# BBB_cape.net
KiCad netlist of a schematic drawn in EAGLE
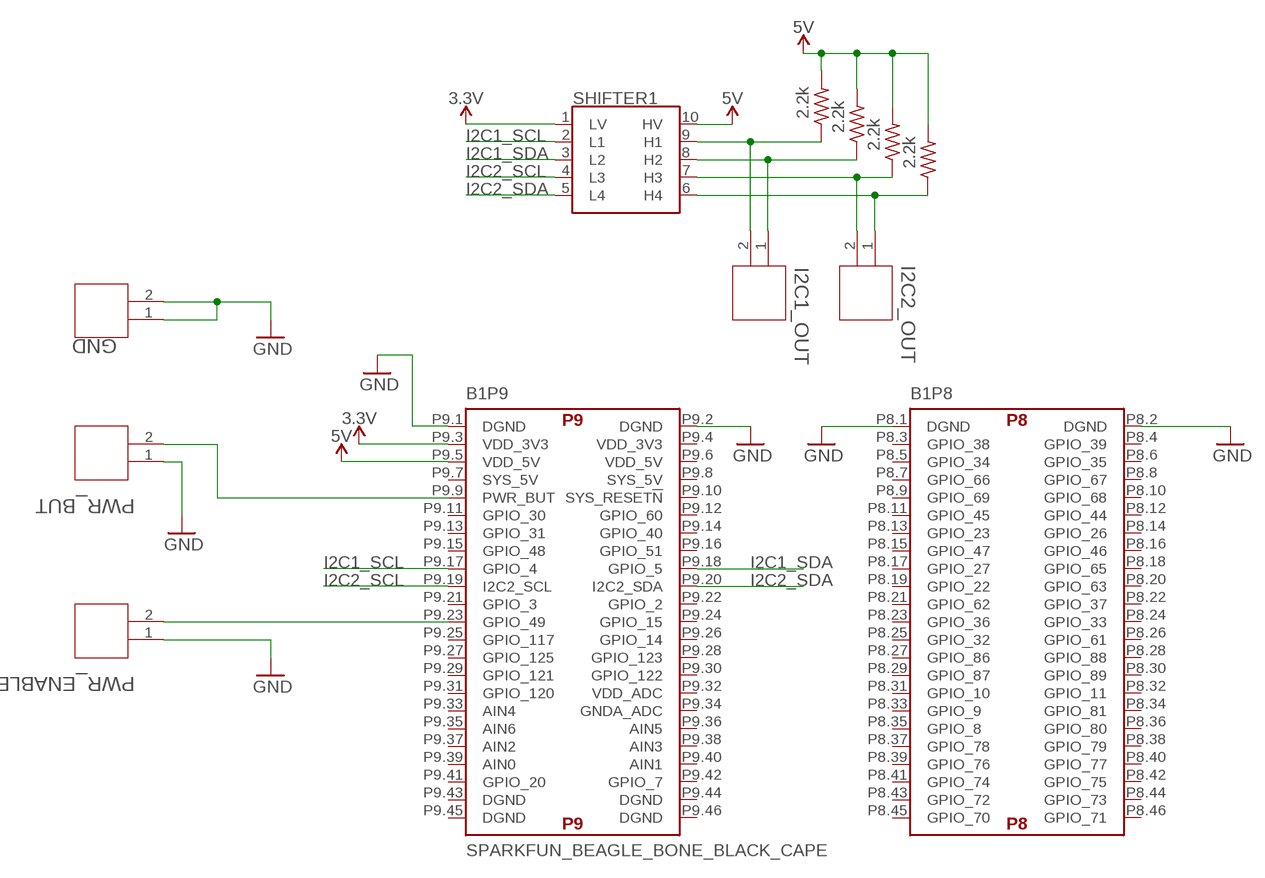
[diagram p0: schematic, sheet 1]

(export (version "E")
  (design (tool "Eeschema 10.0.6"))
  (components
    (comp (ref "B1")
      (value "SPARKFUN_BEAGLE_BONE_BLACK_CAPE")
      (footprint "eagle-import:BEAGLE_BONE_BLACK_CAPE")
      (libsource (lib "eagle-import") (part "SPARKFUN_BEAGLE_BONE_BLACK_CAPE"))
    )
    (comp (ref "GND")
      (value "PHOENIX_CONTACT_1758018")
      (footprint "eagle-import:PHOENIX_CONTACT_1758018")
      (fields
        (field (name "MANUFACTURER_PART_NUMBER") "1758018")
        (field (name "COPYRIGHT") "Copyright (C) 2018 Accelerated Designs. All rights reserved")
      )
      (libsource (lib "eagle-import") (part "PHOENIX_CONTACT_1758018"))
    )
    (comp (ref "I2C1_OUT")
      (value "PHOENIX_CONTACT_1758018")
      (footprint "eagle-import:PHOENIX_CONTACT_1758018")
      (fields
        (field (name "MANUFACTURER_PART_NUMBER") "1758018")
        (field (name "COPYRIGHT") "Copyright (C) 2018 Accelerated Designs. All rights reserved")
      )
      (libsource (lib "eagle-import") (part "PHOENIX_CONTACT_1758018"))
    )
    (comp (ref "I2C2_OUT")
      (value "PHOENIX_CONTACT_1758018")
      (footprint "eagle-import:PHOENIX_CONTACT_1758018")
      (fields
        (field (name "MANUFACTURER_PART_NUMBER") "1758018")
        (field (name "COPYRIGHT") "Copyright (C) 2018 Accelerated Designs. All rights reserved")
      )
      (libsource (lib "eagle-import") (part "PHOENIX_CONTACT_1758018"))
    )
    (comp (ref "PWR_BUT")
      (value "PHOENIX_CONTACT_1758018")
      (footprint "eagle-import:PHOENIX_CONTACT_1758018")
      (fields
        (field (name "MANUFACTURER_PART_NUMBER") "1758018")
        (field (name "COPYRIGHT") "Copyright (C) 2018 Accelerated Designs. All rights reserved")
      )
      (libsource (lib "eagle-import") (part "PHOENIX_CONTACT_1758018"))
    )
    (comp (ref "PWR_ENABLE")
      (value "PHOENIX_CONTACT_1758018")
      (footprint "eagle-import:PHOENIX_CONTACT_1758018")
      (fields
        (field (name "MANUFACTURER_PART_NUMBER") "1758018")
        (field (name "COPYRIGHT") "Copyright (C) 2018 Accelerated Designs. All rights reserved")
      )
      (libsource (lib "eagle-import") (part "PHOENIX_CONTACT_1758018"))
    )
    (comp (ref "R1")
      (value "2.2k")
      (footprint "eagle-import:0204_7")
      (libsource (lib "eagle-import") (part "R-US_0204/7"))
    )
    (comp (ref "R2")
      (value "2.2k")
      (footprint "eagle-import:0204_7")
      (libsource (lib "eagle-import") (part "R-US_0204/7"))
    )
    (comp (ref "R3")
      (value "2.2k")
      (footprint "eagle-import:0204_7")
      (libsource (lib "eagle-import") (part "R-US_0204/7"))
    )
    (comp (ref "R4")
      (value "2.2k")
      (footprint "eagle-import:0204_7")
      (libsource (lib "eagle-import") (part "R-US_0204/7"))
    )
    (comp (ref "SHIFTER1")
      (value "POLOLU_LOGIC_SHIFTERPOLOLU")
      (footprint "eagle-import:POLOLU_LOGIC_SHIFTER")
      (libsource (lib "eagle-import") (part "POLOLU_LOGIC_SHIFTERPOLOLU"))
    )
  )
  (nets
    (net (code "1") (name "/I2C1_SCL") (class "Default")
      (node (ref "B1") (pin "P9.17") (pinfunction "GPIO_4_P9.17") (pintype "bidirectional"))
      (node (ref "SHIFTER1") (pin "2") (pinfunction "L1_2") (pintype "bidirectional"))
    )
    (net (code "2") (name "/I2C1_SDA") (class "Default")
      (node (ref "B1") (pin "P9.18") (pinfunction "GPIO_5_P9.18") (pintype "bidirectional"))
      (node (ref "SHIFTER1") (pin "3") (pinfunction "L2_3") (pintype "bidirectional"))
    )
    (net (code "3") (name "/I2C2_SCL") (class "Default")
      (node (ref "B1") (pin "P9.19") (pinfunction "I2C2_SCL_P9.19") (pintype "bidirectional"))
      (node (ref "SHIFTER1") (pin "4") (pinfunction "L3_4") (pintype "bidirectional"))
    )
    (net (code "4") (name "/I2C2_SDA") (class "Default")
      (node (ref "B1") (pin "P9.20") (pinfunction "I2C2_SDA_P9.20") (pintype "bidirectional"))
      (node (ref "SHIFTER1") (pin "5") (pinfunction "L4_5") (pintype "bidirectional"))
    )
    (net (code "5") (name "3.3V") (class "Default")
      (node (ref "B1") (pin "P9.3") (pinfunction "VDD_3V3_P9.3") (pintype "bidirectional"))
      (node (ref "SHIFTER1") (pin "1") (pinfunction "LV_1") (pintype "input"))
    )
    (net (code "6") (name "5V") (class "Default")
      (node (ref "B1") (pin "P9.5") (pinfunction "VDD_5V_P9.5") (pintype "bidirectional"))
      (node (ref "R1") (pin "2") (pinfunction "2_2") (pintype "passive"))
      (node (ref "R2") (pin "2") (pinfunction "2_2") (pintype "passive"))
      (node (ref "R3") (pin "2") (pinfunction "2_2") (pintype "passive"))
      (node (ref "R4") (pin "2") (pinfunction "2_2") (pintype "passive"))
      (node (ref "SHIFTER1") (pin "10") (pinfunction "HV_10") (pintype "input"))
    )
    (net (code "7") (name "GND") (class "Default")
      (node (ref "B1") (pin "P8.1") (pinfunction "DGND_P8.1") (pintype "bidirectional"))
      (node (ref "B1") (pin "P8.2") (pinfunction "DGND_P8.2") (pintype "bidirectional"))
      (node (ref "B1") (pin "P9.1") (pinfunction "DGND_P9.1") (pintype "bidirectional"))
      (node (ref "B1") (pin "P9.2") (pinfunction "DGND_P9.2") (pintype "bidirectional"))
      (node (ref "GND") (pin "1") (pinfunction "1_1") (pintype "passive"))
      (node (ref "GND") (pin "2") (pinfunction "2_2") (pintype "passive"))
      (node (ref "PWR_BUT") (pin "1") (pinfunction "1_1") (pintype "passive"))
      (node (ref "PWR_ENABLE") (pin "1") (pinfunction "1_1") (pintype "passive"))
    )
    (net (code "8") (name "Net-(B1B-GPIO_49)") (class "Default")
      (node (ref "B1") (pin "P9.23") (pinfunction "GPIO_49_P9.23") (pintype "bidirectional"))
      (node (ref "PWR_ENABLE") (pin "2") (pinfunction "2_2") (pintype "passive"))
    )
    (net (code "9") (name "Net-(B1B-PWR_BUT)") (class "Default")
      (node (ref "B1") (pin "P9.9") (pinfunction "PWR_BUT_P9.9") (pintype "bidirectional"))
      (node (ref "PWR_BUT") (pin "2") (pinfunction "2_2") (pintype "passive"))
    )
    (net (code "10") (name "Net-(SHIFTER1-H1)") (class "Default")
      (node (ref "I2C1_OUT") (pin "2") (pinfunction "2_2") (pintype "passive"))
      (node (ref "R1") (pin "1") (pinfunction "1_1") (pintype "passive"))
      (node (ref "SHIFTER1") (pin "9") (pinfunction "H1_9") (pintype "bidirectional"))
    )
    (net (code "11") (name "Net-(SHIFTER1-H2)") (class "Default")
      (node (ref "I2C1_OUT") (pin "1") (pinfunction "1_1") (pintype "passive"))
      (node (ref "R2") (pin "1") (pinfunction "1_1") (pintype "passive"))
      (node (ref "SHIFTER1") (pin "8") (pinfunction "H2_8") (pintype "bidirectional"))
    )
    (net (code "12") (name "Net-(SHIFTER1-H3)") (class "Default")
      (node (ref "I2C2_OUT") (pin "2") (pinfunction "2_2") (pintype "passive"))
      (node (ref "R3") (pin "1") (pinfunction "1_1") (pintype "passive"))
      (node (ref "SHIFTER1") (pin "7") (pinfunction "H3_7") (pintype "bidirectional"))
    )
    (net (code "13") (name "Net-(SHIFTER1-H4)") (class "Default")
      (node (ref "I2C2_OUT") (pin "1") (pinfunction "1_1") (pintype "passive"))
      (node (ref "R4") (pin "1") (pinfunction "1_1") (pintype "passive"))
      (node (ref "SHIFTER1") (pin "6") (pinfunction "H4_6") (pintype "bidirectional"))
    )
    (net (code "14") (name "unconnected-(B1A-GPIO_8-PadP8.35)") (class "Default")
      (node (ref "B1") (pin "P8.35") (pinfunction "GPIO_8_P8.35") (pintype "bidirectional"))
    )
    (net (code "15") (name "unconnected-(B1A-GPIO_9-PadP8.33)") (class "Default")
      (node (ref "B1") (pin "P8.33") (pinfunction "GPIO_9_P8.33") (pintype "bidirectional"))
    )
    (net (code "16") (name "unconnected-(B1A-GPIO_10-PadP8.31)") (class "Default")
      (node (ref "B1") (pin "P8.31") (pinfunction "GPIO_10_P8.31") (pintype "bidirectional"))
    )
    (net (code "17") (name "unconnected-(B1A-GPIO_11-PadP8.32)") (class "Default")
      (node (ref "B1") (pin "P8.32") (pinfunction "GPIO_11_P8.32") (pintype "bidirectional"))
    )
    (net (code "18") (name "unconnected-(B1A-GPIO_22-PadP8.19)") (class "Default")
      (node (ref "B1") (pin "P8.19") (pinfunction "GPIO_22_P8.19") (pintype "bidirectional"))
    )
    (net (code "19") (name "unconnected-(B1A-GPIO_23-PadP8.13)") (class "Default")
      (node (ref "B1") (pin "P8.13") (pinfunction "GPIO_23_P8.13") (pintype "bidirectional"))
    )
    (net (code "20") (name "unconnected-(B1A-GPIO_26-PadP8.14)") (class "Default")
      (node (ref "B1") (pin "P8.14") (pinfunction "GPIO_26_P8.14") (pintype "bidirectional"))
    )
    (net (code "21") (name "unconnected-(B1A-GPIO_27-PadP8.17)") (class "Default")
      (node (ref "B1") (pin "P8.17") (pinfunction "GPIO_27_P8.17") (pintype "bidirectional"))
    )
    (net (code "22") (name "unconnected-(B1A-GPIO_32-PadP8.25)") (class "Default")
      (node (ref "B1") (pin "P8.25") (pinfunction "GPIO_32_P8.25") (pintype "bidirectional"))
    )
    (net (code "23") (name "unconnected-(B1A-GPIO_33-PadP8.24)") (class "Default")
      (node (ref "B1") (pin "P8.24") (pinfunction "GPIO_33_P8.24") (pintype "bidirectional"))
    )
    (net (code "24") (name "unconnected-(B1A-GPIO_34-PadP8.5)") (class "Default")
      (node (ref "B1") (pin "P8.5") (pinfunction "GPIO_34_P8.5") (pintype "bidirectional"))
    )
    (net (code "25") (name "unconnected-(B1A-GPIO_35-PadP8.6)") (class "Default")
      (node (ref "B1") (pin "P8.6") (pinfunction "GPIO_35_P8.6") (pintype "bidirectional"))
    )
    (net (code "26") (name "unconnected-(B1A-GPIO_36-PadP8.23)") (class "Default")
      (node (ref "B1") (pin "P8.23") (pinfunction "GPIO_36_P8.23") (pintype "bidirectional"))
    )
    (net (code "27") (name "unconnected-(B1A-GPIO_37-PadP8.22)") (class "Default")
      (node (ref "B1") (pin "P8.22") (pinfunction "GPIO_37_P8.22") (pintype "bidirectional"))
    )
    (net (code "28") (name "unconnected-(B1A-GPIO_38-PadP8.3)") (class "Default")
      (node (ref "B1") (pin "P8.3") (pinfunction "GPIO_38_P8.3") (pintype "bidirectional"))
    )
    (net (code "29") (name "unconnected-(B1A-GPIO_39-PadP8.4)") (class "Default")
      (node (ref "B1") (pin "P8.4") (pinfunction "GPIO_39_P8.4") (pintype "bidirectional"))
    )
    (net (code "30") (name "unconnected-(B1A-GPIO_44-PadP8.12)") (class "Default")
      (node (ref "B1") (pin "P8.12") (pinfunction "GPIO_44_P8.12") (pintype "bidirectional"))
    )
    (net (code "31") (name "unconnected-(B1A-GPIO_45-PadP8.11)") (class "Default")
      (node (ref "B1") (pin "P8.11") (pinfunction "GPIO_45_P8.11") (pintype "bidirectional"))
    )
    (net (code "32") (name "unconnected-(B1A-GPIO_46-PadP8.16)") (class "Default")
      (node (ref "B1") (pin "P8.16") (pinfunction "GPIO_46_P8.16") (pintype "bidirectional"))
    )
    (net (code "33") (name "unconnected-(B1A-GPIO_47-PadP8.15)") (class "Default")
      (node (ref "B1") (pin "P8.15") (pinfunction "GPIO_47_P8.15") (pintype "bidirectional"))
    )
    (net (code "34") (name "unconnected-(B1A-GPIO_61-PadP8.26)") (class "Default")
      (node (ref "B1") (pin "P8.26") (pinfunction "GPIO_61_P8.26") (pintype "bidirectional"))
    )
    (net (code "35") (name "unconnected-(B1A-GPIO_62-PadP8.21)") (class "Default")
      (node (ref "B1") (pin "P8.21") (pinfunction "GPIO_62_P8.21") (pintype "bidirectional"))
    )
    (net (code "36") (name "unconnected-(B1A-GPIO_63-PadP8.20)") (class "Default")
      (node (ref "B1") (pin "P8.20") (pinfunction "GPIO_63_P8.20") (pintype "bidirectional"))
    )
    (net (code "37") (name "unconnected-(B1A-GPIO_65-PadP8.18)") (class "Default")
      (node (ref "B1") (pin "P8.18") (pinfunction "GPIO_65_P8.18") (pintype "bidirectional"))
    )
    (net (code "38") (name "unconnected-(B1A-GPIO_66-PadP8.7)") (class "Default")
      (node (ref "B1") (pin "P8.7") (pinfunction "GPIO_66_P8.7") (pintype "bidirectional"))
    )
    (net (code "39") (name "unconnected-(B1A-GPIO_67-PadP8.8)") (class "Default")
      (node (ref "B1") (pin "P8.8") (pinfunction "GPIO_67_P8.8") (pintype "bidirectional"))
    )
    (net (code "40") (name "unconnected-(B1A-GPIO_68-PadP8.10)") (class "Default")
      (node (ref "B1") (pin "P8.10") (pinfunction "GPIO_68_P8.10") (pintype "bidirectional"))
    )
    (net (code "41") (name "unconnected-(B1A-GPIO_69-PadP8.9)") (class "Default")
      (node (ref "B1") (pin "P8.9") (pinfunction "GPIO_69_P8.9") (pintype "bidirectional"))
    )
    (net (code "42") (name "unconnected-(B1A-GPIO_70-PadP8.45)") (class "Default")
      (node (ref "B1") (pin "P8.45") (pinfunction "GPIO_70_P8.45") (pintype "bidirectional"))
    )
    (net (code "43") (name "unconnected-(B1A-GPIO_71-PadP8.46)") (class "Default")
      (node (ref "B1") (pin "P8.46") (pinfunction "GPIO_71_P8.46") (pintype "bidirectional"))
    )
    (net (code "44") (name "unconnected-(B1A-GPIO_72-PadP8.43)") (class "Default")
      (node (ref "B1") (pin "P8.43") (pinfunction "GPIO_72_P8.43") (pintype "bidirectional"))
    )
    (net (code "45") (name "unconnected-(B1A-GPIO_73-PadP8.44)") (class "Default")
      (node (ref "B1") (pin "P8.44") (pinfunction "GPIO_73_P8.44") (pintype "bidirectional"))
    )
    (net (code "46") (name "unconnected-(B1A-GPIO_74-PadP8.41)") (class "Default")
      (node (ref "B1") (pin "P8.41") (pinfunction "GPIO_74_P8.41") (pintype "bidirectional"))
    )
    (net (code "47") (name "unconnected-(B1A-GPIO_75-PadP8.42)") (class "Default")
      (node (ref "B1") (pin "P8.42") (pinfunction "GPIO_75_P8.42") (pintype "bidirectional"))
    )
    (net (code "48") (name "unconnected-(B1A-GPIO_76-PadP8.39)") (class "Default")
      (node (ref "B1") (pin "P8.39") (pinfunction "GPIO_76_P8.39") (pintype "bidirectional"))
    )
    (net (code "49") (name "unconnected-(B1A-GPIO_77-PadP8.40)") (class "Default")
      (node (ref "B1") (pin "P8.40") (pinfunction "GPIO_77_P8.40") (pintype "bidirectional"))
    )
    (net (code "50") (name "unconnected-(B1A-GPIO_78-PadP8.37)") (class "Default")
      (node (ref "B1") (pin "P8.37") (pinfunction "GPIO_78_P8.37") (pintype "bidirectional"))
    )
    (net (code "51") (name "unconnected-(B1A-GPIO_79-PadP8.38)") (class "Default")
      (node (ref "B1") (pin "P8.38") (pinfunction "GPIO_79_P8.38") (pintype "bidirectional"))
    )
    (net (code "52") (name "unconnected-(B1A-GPIO_80-PadP8.36)") (class "Default")
      (node (ref "B1") (pin "P8.36") (pinfunction "GPIO_80_P8.36") (pintype "bidirectional"))
    )
    (net (code "53") (name "unconnected-(B1A-GPIO_81-PadP8.34)") (class "Default")
      (node (ref "B1") (pin "P8.34") (pinfunction "GPIO_81_P8.34") (pintype "bidirectional"))
    )
    (net (code "54") (name "unconnected-(B1A-GPIO_86-PadP8.27)") (class "Default")
      (node (ref "B1") (pin "P8.27") (pinfunction "GPIO_86_P8.27") (pintype "bidirectional"))
    )
    (net (code "55") (name "unconnected-(B1A-GPIO_87-PadP8.29)") (class "Default")
      (node (ref "B1") (pin "P8.29") (pinfunction "GPIO_87_P8.29") (pintype "bidirectional"))
    )
    (net (code "56") (name "unconnected-(B1A-GPIO_88-PadP8.28)") (class "Default")
      (node (ref "B1") (pin "P8.28") (pinfunction "GPIO_88_P8.28") (pintype "bidirectional"))
    )
    (net (code "57") (name "unconnected-(B1A-GPIO_89-PadP8.30)") (class "Default")
      (node (ref "B1") (pin "P8.30") (pinfunction "GPIO_89_P8.30") (pintype "bidirectional"))
    )
    (net (code "58") (name "unconnected-(B1B-AIN0-PadP9.39)") (class "Default")
      (node (ref "B1") (pin "P9.39") (pinfunction "AIN0_P9.39") (pintype "bidirectional"))
    )
    (net (code "59") (name "unconnected-(B1B-AIN1-PadP9.40)") (class "Default")
      (node (ref "B1") (pin "P9.40") (pinfunction "AIN1_P9.40") (pintype "bidirectional"))
    )
    (net (code "60") (name "unconnected-(B1B-AIN2-PadP9.37)") (class "Default")
      (node (ref "B1") (pin "P9.37") (pinfunction "AIN2_P9.37") (pintype "bidirectional"))
    )
    (net (code "61") (name "unconnected-(B1B-AIN3-PadP9.38)") (class "Default")
      (node (ref "B1") (pin "P9.38") (pinfunction "AIN3_P9.38") (pintype "bidirectional"))
    )
    (net (code "62") (name "unconnected-(B1B-AIN4-PadP9.33)") (class "Default")
      (node (ref "B1") (pin "P9.33") (pinfunction "AIN4_P9.33") (pintype "bidirectional"))
    )
    (net (code "63") (name "unconnected-(B1B-AIN5-PadP9.36)") (class "Default")
      (node (ref "B1") (pin "P9.36") (pinfunction "AIN5_P9.36") (pintype "bidirectional"))
    )
    (net (code "64") (name "unconnected-(B1B-AIN6-PadP9.35)") (class "Default")
      (node (ref "B1") (pin "P9.35") (pinfunction "AIN6_P9.35") (pintype "bidirectional"))
    )
    (net (code "65") (name "unconnected-(B1B-DGND-PadP9.43)") (class "Default")
      (node (ref "B1") (pin "P9.43") (pinfunction "DGND_P9.43") (pintype "bidirectional"))
    )
    (net (code "66") (name "unconnected-(B1B-DGND-PadP9.44)") (class "Default")
      (node (ref "B1") (pin "P9.44") (pinfunction "DGND_P9.44") (pintype "bidirectional"))
    )
    (net (code "67") (name "unconnected-(B1B-DGND-PadP9.45)") (class "Default")
      (node (ref "B1") (pin "P9.45") (pinfunction "DGND_P9.45") (pintype "bidirectional"))
    )
    (net (code "68") (name "unconnected-(B1B-DGND-PadP9.46)") (class "Default")
      (node (ref "B1") (pin "P9.46") (pinfunction "DGND_P9.46") (pintype "bidirectional"))
    )
    (net (code "69") (name "unconnected-(B1B-GNDA_ADC-PadP9.34)") (class "Default")
      (node (ref "B1") (pin "P9.34") (pinfunction "GNDA_ADC_P9.34") (pintype "bidirectional"))
    )
    (net (code "70") (name "unconnected-(B1B-GPIO_2-PadP9.22)") (class "Default")
      (node (ref "B1") (pin "P9.22") (pinfunction "GPIO_2_P9.22") (pintype "bidirectional"))
    )
    (net (code "71") (name "unconnected-(B1B-GPIO_3-PadP9.21)") (class "Default")
      (node (ref "B1") (pin "P9.21") (pinfunction "GPIO_3_P9.21") (pintype "bidirectional"))
    )
    (net (code "72") (name "unconnected-(B1B-GPIO_7-PadP9.42)") (class "Default")
      (node (ref "B1") (pin "P9.42") (pinfunction "GPIO_7_P9.42") (pintype "bidirectional"))
    )
    (net (code "73") (name "unconnected-(B1B-GPIO_14-PadP9.26)") (class "Default")
      (node (ref "B1") (pin "P9.26") (pinfunction "GPIO_14_P9.26") (pintype "bidirectional"))
    )
    (net (code "74") (name "unconnected-(B1B-GPIO_15-PadP9.24)") (class "Default")
      (node (ref "B1") (pin "P9.24") (pinfunction "GPIO_15_P9.24") (pintype "bidirectional"))
    )
    (net (code "75") (name "unconnected-(B1B-GPIO_20-PadP9.41)") (class "Default")
      (node (ref "B1") (pin "P9.41") (pinfunction "GPIO_20_P9.41") (pintype "bidirectional"))
    )
    (net (code "76") (name "unconnected-(B1B-GPIO_30-PadP9.11)") (class "Default")
      (node (ref "B1") (pin "P9.11") (pinfunction "GPIO_30_P9.11") (pintype "bidirectional"))
    )
    (net (code "77") (name "unconnected-(B1B-GPIO_31-PadP9.13)") (class "Default")
      (node (ref "B1") (pin "P9.13") (pinfunction "GPIO_31_P9.13") (pintype "bidirectional"))
    )
    (net (code "78") (name "unconnected-(B1B-GPIO_40-PadP9.14)") (class "Default")
      (node (ref "B1") (pin "P9.14") (pinfunction "GPIO_40_P9.14") (pintype "bidirectional"))
    )
    (net (code "79") (name "unconnected-(B1B-GPIO_48-PadP9.15)") (class "Default")
      (node (ref "B1") (pin "P9.15") (pinfunction "GPIO_48_P9.15") (pintype "bidirectional"))
    )
    (net (code "80") (name "unconnected-(B1B-GPIO_51-PadP9.16)") (class "Default")
      (node (ref "B1") (pin "P9.16") (pinfunction "GPIO_51_P9.16") (pintype "bidirectional"))
    )
    (net (code "81") (name "unconnected-(B1B-GPIO_60-PadP9.12)") (class "Default")
      (node (ref "B1") (pin "P9.12") (pinfunction "GPIO_60_P9.12") (pintype "bidirectional"))
    )
    (net (code "82") (name "unconnected-(B1B-GPIO_117-PadP9.25)") (class "Default")
      (node (ref "B1") (pin "P9.25") (pinfunction "GPIO_117_P9.25") (pintype "bidirectional"))
    )
    (net (code "83") (name "unconnected-(B1B-GPIO_120-PadP9.31)") (class "Default")
      (node (ref "B1") (pin "P9.31") (pinfunction "GPIO_120_P9.31") (pintype "bidirectional"))
    )
    (net (code "84") (name "unconnected-(B1B-GPIO_121-PadP9.29)") (class "Default")
      (node (ref "B1") (pin "P9.29") (pinfunction "GPIO_121_P9.29") (pintype "bidirectional"))
    )
    (net (code "85") (name "unconnected-(B1B-GPIO_122-PadP9.30)") (class "Default")
      (node (ref "B1") (pin "P9.30") (pinfunction "GPIO_122_P9.30") (pintype "bidirectional"))
    )
    (net (code "86") (name "unconnected-(B1B-GPIO_123-PadP9.28)") (class "Default")
      (node (ref "B1") (pin "P9.28") (pinfunction "GPIO_123_P9.28") (pintype "bidirectional"))
    )
    (net (code "87") (name "unconnected-(B1B-GPIO_125-PadP9.27)") (class "Default")
      (node (ref "B1") (pin "P9.27") (pinfunction "GPIO_125_P9.27") (pintype "bidirectional"))
    )
    (net (code "88") (name "unconnected-(B1B-SYS_5V-PadP9.7)") (class "Default")
      (node (ref "B1") (pin "P9.7") (pinfunction "SYS_5V_P9.7") (pintype "bidirectional"))
    )
    (net (code "89") (name "unconnected-(B1B-SYS_5V-PadP9.8)") (class "Default")
      (node (ref "B1") (pin "P9.8") (pinfunction "SYS_5V_P9.8") (pintype "bidirectional"))
    )
    (net (code "90") (name "unconnected-(B1B-SYS_RESET~{N}-PadP9.10)") (class "Default")
      (node (ref "B1") (pin "P9.10") (pinfunction "SYS_RESET~{N}_P9.10") (pintype "bidirectional"))
    )
    (net (code "91") (name "unconnected-(B1B-VDD_3V3-PadP9.4)") (class "Default")
      (node (ref "B1") (pin "P9.4") (pinfunction "VDD_3V3_P9.4") (pintype "bidirectional"))
    )
    (net (code "92") (name "unconnected-(B1B-VDD_5V-PadP9.6)") (class "Default")
      (node (ref "B1") (pin "P9.6") (pinfunction "VDD_5V_P9.6") (pintype "bidirectional"))
    )
    (net (code "93") (name "unconnected-(B1B-VDD_ADC-PadP9.32)") (class "Default")
      (node (ref "B1") (pin "P9.32") (pinfunction "VDD_ADC_P9.32") (pintype "bidirectional"))
    )
  )
)
